# hacker-boards-refactor.net
KiCad netlist of a schematic drawn in EAGLE
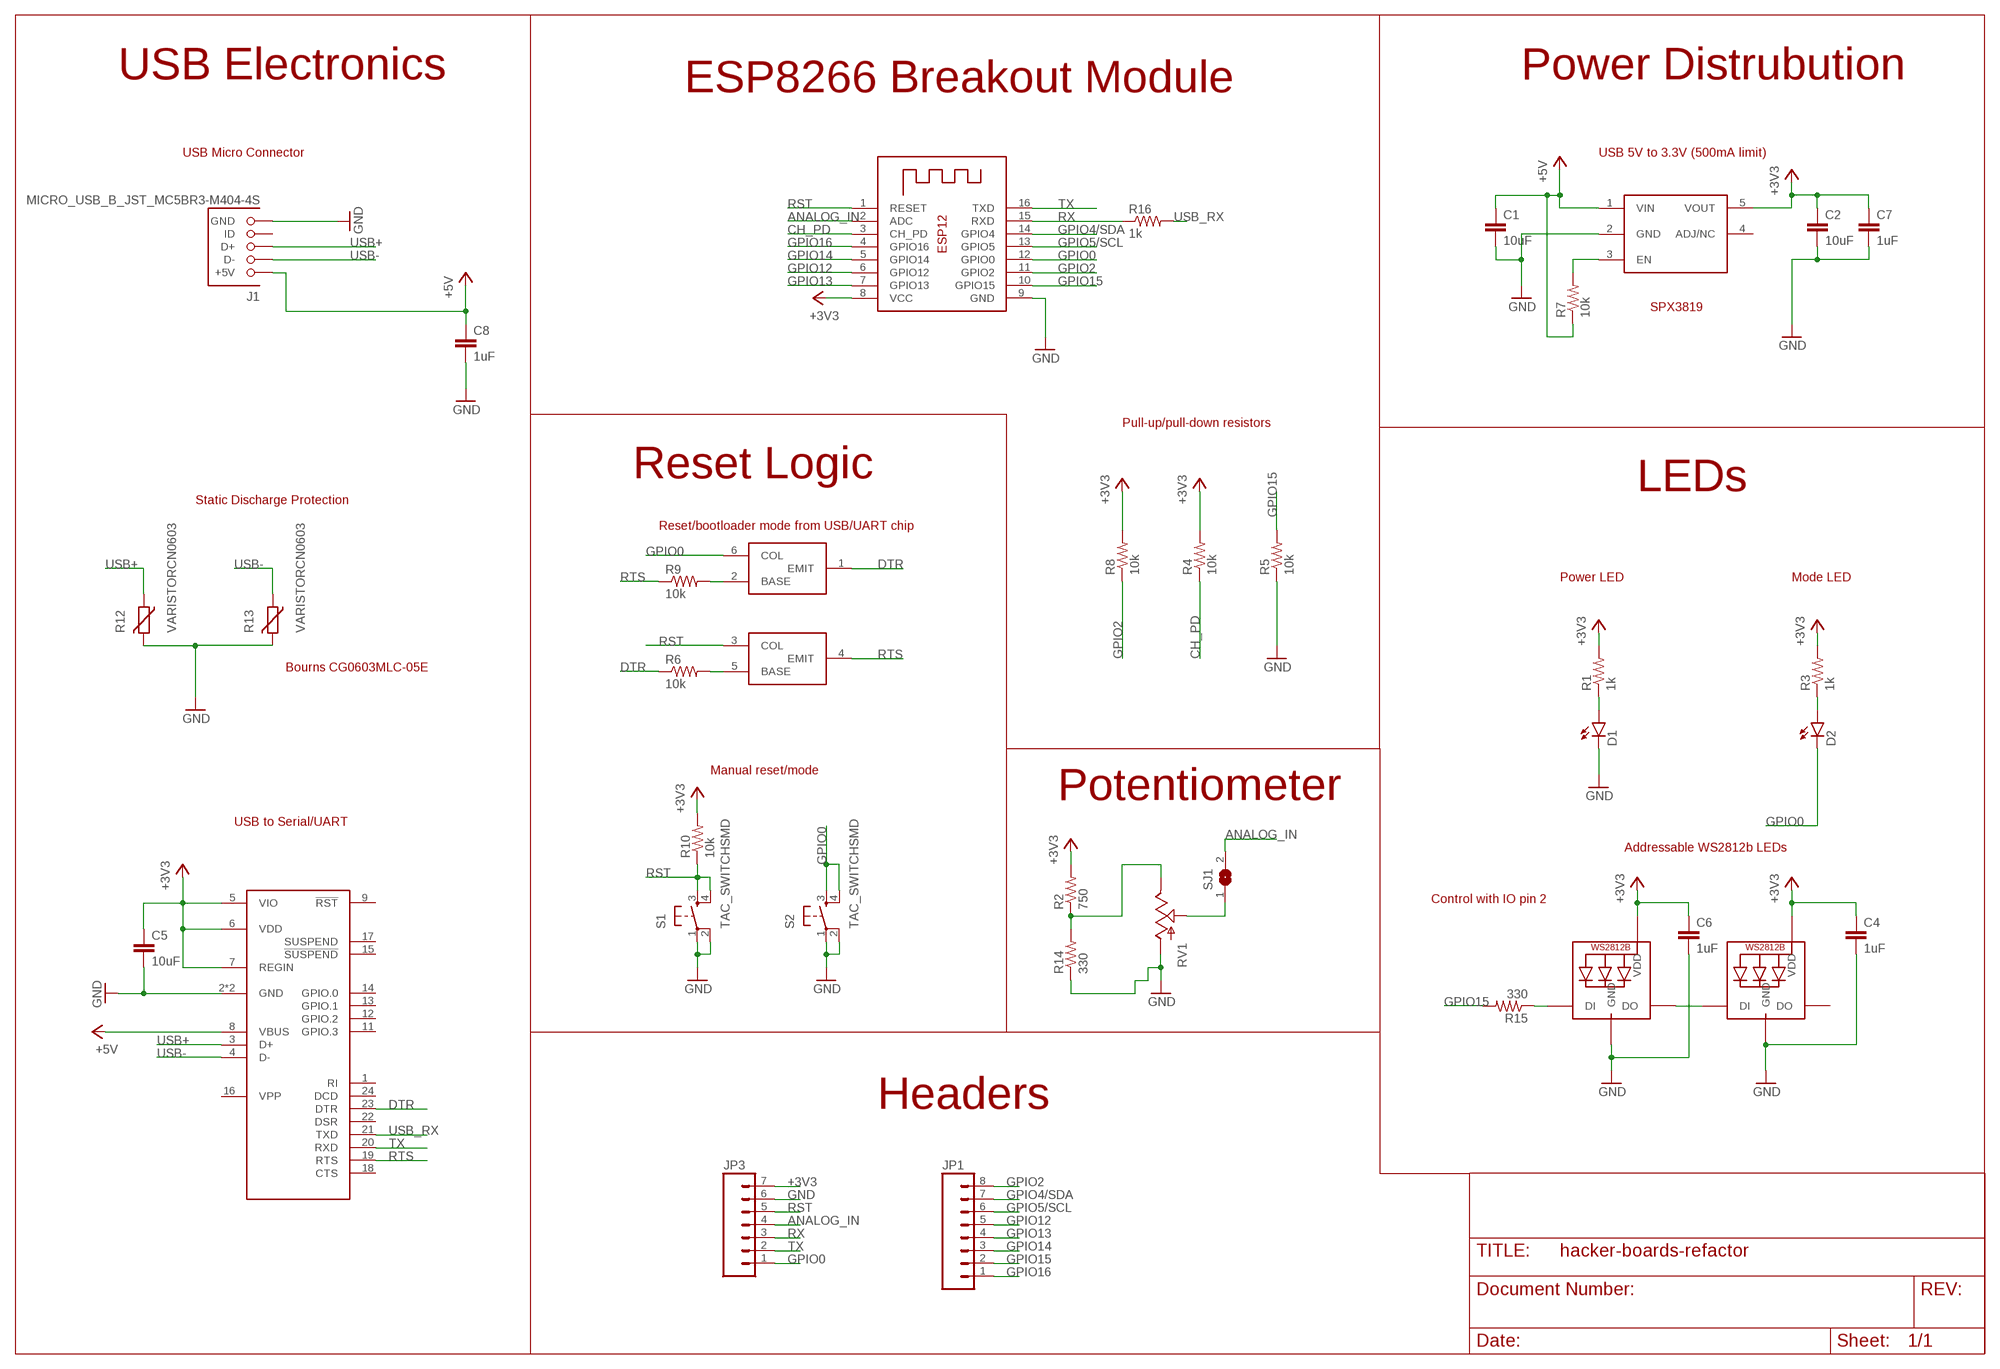
[diagram p0: schematic, sheet 1]

(export (version "E")
  (design (tool "Eeschema 10.0.6"))
  (components
    (comp (ref "C1")
      (value "10uF")
      (footprint "eagle-import:C0805")
      (libsource (lib "eagle-import") (part "C0805"))
    )
    (comp (ref "C2")
      (value "10uF")
      (footprint "eagle-import:C0805")
      (libsource (lib "eagle-import") (part "C0805"))
    )
    (comp (ref "C4")
      (value "1uF")
      (footprint "eagle-import:C0402")
      (libsource (lib "eagle-import") (part "C-EUC0402"))
    )
    (comp (ref "C5")
      (value "10uF")
      (footprint "eagle-import:C0805")
      (libsource (lib "eagle-import") (part "C0805"))
    )
    (comp (ref "C6")
      (value "1uF")
      (footprint "eagle-import:C0402")
      (libsource (lib "eagle-import") (part "C-EUC0402"))
    )
    (comp (ref "C7")
      (value "1uF")
      (footprint "eagle-import:C0402")
      (libsource (lib "eagle-import") (part "C-EUC0402"))
    )
    (comp (ref "C8")
      (value "1uF")
      (footprint "eagle-import:C0402")
      (libsource (lib "eagle-import") (part "C-EUC0402"))
    )
    (comp (ref "D1")
      (value "LED0603")
      (footprint "eagle-import:LED-0603")
      (libsource (lib "eagle-import") (part "LED0603"))
    )
    (comp (ref "D2")
      (value "LED0603")
      (footprint "eagle-import:LED-0603")
      (libsource (lib "eagle-import") (part "LED0603"))
    )
    (comp (ref "J1")
      (value "MICRO_USB_B_JST_MC5BR3-M404-4S")
      (footprint "eagle-import:USB_MICRO_B-JST-MC5BR3-M404-4S-TB")
      (libsource (lib "eagle-import") (part "MICRO_USB_B_JST_MC5BR3-M404-4S"))
    )
    (comp (ref "JP1")
      (value "M08")
      (footprint "eagle-import:1X08_ROUND")
      (libsource (lib "eagle-import") (part "M08"))
    )
    (comp (ref "JP3")
      (value "M07")
      (footprint "eagle-import:1X07")
      (libsource (lib "eagle-import") (part "M07"))
    )
    (comp (ref "LED1")
      (value "WS2812B5050")
      (footprint "eagle-import:WS2812B")
      (libsource (lib "eagle-import") (part "WS2812B5050"))
    )
    (comp (ref "LED2")
      (value "WS2812B5050")
      (footprint "eagle-import:WS2812B")
      (libsource (lib "eagle-import") (part "WS2812B5050"))
    )
    (comp (ref "R1")
      (value "1k")
      (footprint "eagle-import:R0402")
      (libsource (lib "eagle-import") (part "R-US_R0402"))
    )
    (comp (ref "R2")
      (value "750")
      (footprint "eagle-import:R0402")
      (libsource (lib "eagle-import") (part "R-US_R0402"))
    )
    (comp (ref "R3")
      (value "1k")
      (footprint "eagle-import:R0402")
      (libsource (lib "eagle-import") (part "R-US_R0402"))
    )
    (comp (ref "R4")
      (value "10k")
      (footprint "eagle-import:R0402")
      (libsource (lib "eagle-import") (part "R-US_R0402"))
    )
    (comp (ref "R5")
      (value "10k")
      (footprint "eagle-import:R0402")
      (libsource (lib "eagle-import") (part "R-US_R0402"))
    )
    (comp (ref "R6")
      (value "10k")
      (footprint "eagle-import:R0402")
      (libsource (lib "eagle-import") (part "R-US_R0402"))
    )
    (comp (ref "R7")
      (value "10k")
      (footprint "eagle-import:R0402")
      (libsource (lib "eagle-import") (part "R-US_R0402"))
    )
    (comp (ref "R8")
      (value "10k")
      (footprint "eagle-import:R0402")
      (libsource (lib "eagle-import") (part "R-US_R0402"))
    )
    (comp (ref "R9")
      (value "10k")
      (footprint "eagle-import:R0402")
      (libsource (lib "eagle-import") (part "R-US_R0402"))
    )
    (comp (ref "R10")
      (value "10k")
      (footprint "eagle-import:R0402")
      (libsource (lib "eagle-import") (part "R-US_R0402"))
    )
    (comp (ref "R12")
      (value "VARISTORCN0603")
      (footprint "eagle-import:CT_CN0603")
      (libsource (lib "eagle-import") (part "VARISTORCN0603"))
    )
    (comp (ref "R13")
      (value "VARISTORCN0603")
      (footprint "eagle-import:CT_CN0603")
      (libsource (lib "eagle-import") (part "VARISTORCN0603"))
    )
    (comp (ref "R14")
      (value "330")
      (footprint "eagle-import:R0402")
      (libsource (lib "eagle-import") (part "R-US_R0402"))
    )
    (comp (ref "R15")
      (value "330")
      (footprint "eagle-import:R0402")
      (libsource (lib "eagle-import") (part "R-US_R0402"))
    )
    (comp (ref "R16")
      (value "1k")
      (footprint "eagle-import:R0402")
      (libsource (lib "eagle-import") (part "R-US_R0402"))
    )
    (comp (ref "RV1")
      (value "POTALPS-KIT")
      (footprint "eagle-import:ALPS_POT_KIT")
      (libsource (lib "eagle-import") (part "POTALPS-KIT"))
    )
    (comp (ref "S1")
      (value "TAC_SWITCHSMD")
      (footprint "eagle-import:TACTILE-SWITCH-SMD")
      (libsource (lib "eagle-import") (part "TAC_SWITCHSMD"))
    )
    (comp (ref "S2")
      (value "TAC_SWITCHSMD")
      (footprint "eagle-import:TACTILE-SWITCH-SMD")
      (libsource (lib "eagle-import") (part "TAC_SWITCHSMD"))
    )
    (comp (ref "SJ1") (value "SJ") (footprint "eagle-import:SJ") (libsource (lib "eagle-import") (part "SJ")))
    (comp (ref "U$2")
      (value "AP2112")
      (footprint "eagle-import:SOT23-5L")
      (libsource (lib "eagle-import") (part "AP2112"))
    )
    (comp (ref "U$3")
      (value "CP2104")
      (footprint "eagle-import:QFN24_4X4")
      (libsource (lib "eagle-import") (part "CP2104"))
    )
    (comp (ref "U$4")
      (value "MBT3904DW1T1G")
      (footprint "eagle-import:SOT363")
      (libsource (lib "eagle-import") (part "MBT3904DW1T1G"))
    )
    (comp (ref "X1")
      (value "ESP-12")
      (footprint "eagle-import:ESP-12")
      (libsource (lib "eagle-import") (part "ESP-12"))
    )
  )
  (nets
    (net (code "1") (name "+3V3") (class "Default")
      (node (ref "C2") (pin "1") (pinfunction "1_1") (pintype "passive"))
      (node (ref "C4") (pin "1") (pinfunction "1_1") (pintype "passive"))
      (node (ref "C5") (pin "1") (pinfunction "1_1") (pintype "passive"))
      (node (ref "C6") (pin "1") (pinfunction "1_1") (pintype "passive"))
      (node (ref "C7") (pin "1") (pinfunction "1_1") (pintype "passive"))
      (node (ref "JP3") (pin "7") (pinfunction "7_7") (pintype "passive"))
      (node (ref "LED1") (pin "1-VDD") (pinfunction "VDD_1-VDD") (pintype "power_in"))
      (node (ref "LED2") (pin "1-VDD") (pinfunction "VDD_1-VDD") (pintype "power_in"))
      (node (ref "R1") (pin "2") (pinfunction "2_2") (pintype "passive"))
      (node (ref "R10") (pin "2") (pinfunction "2_2") (pintype "passive"))
      (node (ref "R2") (pin "2") (pinfunction "2_2") (pintype "passive"))
      (node (ref "R3") (pin "2") (pinfunction "2_2") (pintype "passive"))
      (node (ref "R4") (pin "2") (pinfunction "2_2") (pintype "passive"))
      (node (ref "R8") (pin "2") (pinfunction "2_2") (pintype "passive"))
      (node (ref "U$2") (pin "5") (pinfunction "VOUT_5") (pintype "bidirectional"))
      (node (ref "U$3") (pin "5") (pinfunction "VIO_5") (pintype "bidirectional"))
      (node (ref "U$3") (pin "6") (pinfunction "VDD_6") (pintype "bidirectional"))
      (node (ref "U$3") (pin "7") (pinfunction "REGIN_7") (pintype "bidirectional"))
      (node (ref "X1") (pin "8") (pinfunction "VCC_8") (pintype "power_in"))
    )
    (net (code "2") (name "+5V") (class "Default")
      (node (ref "C1") (pin "1") (pinfunction "1_1") (pintype "passive"))
      (node (ref "C8") (pin "1") (pinfunction "1_1") (pintype "passive"))
      (node (ref "J1") (pin "1") (pinfunction "+5V_1") (pintype "bidirectional"))
      (node (ref "R7") (pin "1") (pinfunction "1_1") (pintype "passive"))
      (node (ref "U$2") (pin "1") (pinfunction "VIN_1") (pintype "bidirectional"))
      (node (ref "U$3") (pin "8") (pinfunction "VBUS_8") (pintype "bidirectional"))
    )
    (net (code "3") (name "/ANALOG_IN") (class "Default")
      (node (ref "JP3") (pin "4") (pinfunction "4_4") (pintype "passive"))
      (node (ref "SJ1") (pin "2") (pinfunction "2_2") (pintype "passive"))
      (node (ref "X1") (pin "2") (pinfunction "ADC_2") (pintype "passive"))
    )
    (net (code "4") (name "/CH_PD") (class "Default")
      (node (ref "R4") (pin "1") (pinfunction "1_1") (pintype "passive"))
      (node (ref "X1") (pin "3") (pinfunction "CH_PD_3") (pintype "input"))
    )
    (net (code "5") (name "/DTR") (class "Default")
      (node (ref "R6") (pin "1") (pinfunction "1_1") (pintype "passive"))
      (node (ref "U$3") (pin "23") (pinfunction "DTR_23") (pintype "bidirectional"))
      (node (ref "U$4") (pin "1") (pinfunction "EMIT_1") (pintype "bidirectional"))
    )
    (net (code "6") (name "/GPIO0") (class "Default")
      (node (ref "D2") (pin "C") (pinfunction "C_C") (pintype "passive"))
      (node (ref "JP3") (pin "1") (pinfunction "1_1") (pintype "passive"))
      (node (ref "S2") (pin "3") (pinfunction "3_3") (pintype "passive"))
      (node (ref "S2") (pin "4") (pinfunction "4_4") (pintype "passive"))
      (node (ref "U$4") (pin "6") (pinfunction "COL_6") (pintype "bidirectional"))
      (node (ref "X1") (pin "12") (pinfunction "GPIO0_12") (pintype "bidirectional"))
    )
    (net (code "7") (name "/GPIO2") (class "Default")
      (node (ref "JP1") (pin "8") (pinfunction "8_8") (pintype "passive"))
      (node (ref "R8") (pin "1") (pinfunction "1_1") (pintype "passive"))
      (node (ref "X1") (pin "11") (pinfunction "GPIO2_11") (pintype "bidirectional"))
    )
    (net (code "8") (name "/GPIO4{slash}SDA") (class "Default")
      (node (ref "JP1") (pin "7") (pinfunction "7_7") (pintype "passive"))
      (node (ref "X1") (pin "14") (pinfunction "GPIO4_14") (pintype "bidirectional"))
    )
    (net (code "9") (name "/GPIO5{slash}SCL") (class "Default")
      (node (ref "JP1") (pin "6") (pinfunction "6_6") (pintype "passive"))
      (node (ref "X1") (pin "13") (pinfunction "GPIO5_13") (pintype "bidirectional"))
    )
    (net (code "10") (name "/GPIO12") (class "Default")
      (node (ref "JP1") (pin "5") (pinfunction "5_5") (pintype "passive"))
      (node (ref "X1") (pin "6") (pinfunction "GPIO12_6") (pintype "bidirectional"))
    )
    (net (code "11") (name "/GPIO13") (class "Default")
      (node (ref "JP1") (pin "4") (pinfunction "4_4") (pintype "passive"))
      (node (ref "X1") (pin "7") (pinfunction "GPIO13_7") (pintype "bidirectional"))
    )
    (net (code "12") (name "/GPIO14") (class "Default")
      (node (ref "JP1") (pin "3") (pinfunction "3_3") (pintype "passive"))
      (node (ref "X1") (pin "5") (pinfunction "GPIO14_5") (pintype "bidirectional"))
    )
    (net (code "13") (name "/GPIO15") (class "Default")
      (node (ref "JP1") (pin "2") (pinfunction "2_2") (pintype "passive"))
      (node (ref "R15") (pin "2") (pinfunction "2_2") (pintype "passive"))
      (node (ref "R5") (pin "2") (pinfunction "2_2") (pintype "passive"))
      (node (ref "X1") (pin "10") (pinfunction "GPIO15_10") (pintype "bidirectional"))
    )
    (net (code "14") (name "/GPIO16") (class "Default")
      (node (ref "JP1") (pin "1") (pinfunction "1_1") (pintype "passive"))
      (node (ref "X1") (pin "4") (pinfunction "GPIO16_4") (pintype "bidirectional"))
    )
    (net (code "15") (name "/RST") (class "Default")
      (node (ref "JP3") (pin "5") (pinfunction "5_5") (pintype "passive"))
      (node (ref "R10") (pin "1") (pinfunction "1_1") (pintype "passive"))
      (node (ref "S1") (pin "3") (pinfunction "3_3") (pintype "passive"))
      (node (ref "S1") (pin "4") (pinfunction "4_4") (pintype "passive"))
      (node (ref "U$4") (pin "3") (pinfunction "COL_3") (pintype "bidirectional"))
      (node (ref "X1") (pin "1") (pinfunction "RESET_1") (pintype "input"))
    )
    (net (code "16") (name "/RTS") (class "Default")
      (node (ref "R9") (pin "1") (pinfunction "1_1") (pintype "passive"))
      (node (ref "U$3") (pin "19") (pinfunction "RTS_19") (pintype "bidirectional"))
      (node (ref "U$4") (pin "4") (pinfunction "EMIT_4") (pintype "bidirectional"))
    )
    (net (code "17") (name "/RX") (class "Default")
      (node (ref "JP3") (pin "3") (pinfunction "3_3") (pintype "passive"))
      (node (ref "R16") (pin "1") (pinfunction "1_1") (pintype "passive"))
      (node (ref "X1") (pin "15") (pinfunction "RXD_15") (pintype "input"))
    )
    (net (code "18") (name "/TX") (class "Default")
      (node (ref "JP3") (pin "2") (pinfunction "2_2") (pintype "passive"))
      (node (ref "U$3") (pin "20") (pinfunction "RXD_20") (pintype "bidirectional"))
      (node (ref "X1") (pin "16") (pinfunction "TXD_16") (pintype "output"))
    )
    (net (code "19") (name "/USB+") (class "Default")
      (node (ref "J1") (pin "3") (pinfunction "D+_3") (pintype "bidirectional"))
      (node (ref "R12") (pin "1") (pinfunction "1_1") (pintype "passive"))
      (node (ref "U$3") (pin "3") (pinfunction "D+_3") (pintype "bidirectional"))
    )
    (net (code "20") (name "/USB-") (class "Default")
      (node (ref "J1") (pin "2") (pinfunction "D-_2") (pintype "bidirectional"))
      (node (ref "R13") (pin "1") (pinfunction "1_1") (pintype "passive"))
      (node (ref "U$3") (pin "4") (pinfunction "D-_4") (pintype "bidirectional"))
    )
    (net (code "21") (name "/USB_RX") (class "Default")
      (node (ref "R16") (pin "2") (pinfunction "2_2") (pintype "passive"))
      (node (ref "U$3") (pin "21") (pinfunction "TXD_21") (pintype "bidirectional"))
    )
    (net (code "22") (name "GND") (class "Default")
      (node (ref "C1") (pin "2") (pinfunction "2_2") (pintype "passive"))
      (node (ref "C2") (pin "2") (pinfunction "2_2") (pintype "passive"))
      (node (ref "C4") (pin "2") (pinfunction "2_2") (pintype "passive"))
      (node (ref "C5") (pin "2") (pinfunction "2_2") (pintype "passive"))
      (node (ref "C6") (pin "2") (pinfunction "2_2") (pintype "passive"))
      (node (ref "C7") (pin "2") (pinfunction "2_2") (pintype "passive"))
      (node (ref "C8") (pin "2") (pinfunction "2_2") (pintype "passive"))
      (node (ref "D1") (pin "C") (pinfunction "C_C") (pintype "passive"))
      (node (ref "J1") (pin "5") (pinfunction "GND_5") (pintype "bidirectional"))
      (node (ref "JP3") (pin "6") (pinfunction "6_6") (pintype "passive"))
      (node (ref "LED1") (pin "3-GND") (pinfunction "GND_3-GND") (pintype "power_in"))
      (node (ref "LED2") (pin "3-GND") (pinfunction "GND_3-GND") (pintype "power_in"))
      (node (ref "R12") (pin "2") (pinfunction "2_2") (pintype "passive"))
      (node (ref "R13") (pin "2") (pinfunction "2_2") (pintype "passive"))
      (node (ref "R14") (pin "1") (pinfunction "1_1") (pintype "passive"))
      (node (ref "R5") (pin "1") (pinfunction "1_1") (pintype "passive"))
      (node (ref "RV1") (pin "P$3") (pinfunction "A_P$3") (pintype "passive"))
      (node (ref "S1") (pin "1") (pinfunction "1_1") (pintype "passive"))
      (node (ref "S1") (pin "2") (pinfunction "2_2") (pintype "passive"))
      (node (ref "S2") (pin "1") (pinfunction "1_1") (pintype "passive"))
      (node (ref "S2") (pin "2") (pinfunction "2_2") (pintype "passive"))
      (node (ref "U$2") (pin "2") (pinfunction "GND_2") (pintype "bidirectional"))
      (node (ref "U$3") (pin "2") (pinfunction "GND_2") (pintype "bidirectional"))
      (node (ref "U$3") (pin "25") (pinfunction "GND_25") (pintype "bidirectional"))
      (node (ref "X1") (pin "9") (pinfunction "GND_9") (pintype "power_in"))
    )
    (net (code "23") (name "Net-(D1-PadA)") (class "Default")
      (node (ref "D1") (pin "A") (pinfunction "A_A") (pintype "passive"))
      (node (ref "R1") (pin "1") (pinfunction "1_1") (pintype "passive"))
    )
    (net (code "24") (name "Net-(D2-PadA)") (class "Default")
      (node (ref "D2") (pin "A") (pinfunction "A_A") (pintype "passive"))
      (node (ref "R3") (pin "1") (pinfunction "1_1") (pintype "passive"))
    )
    (net (code "25") (name "Net-(LED1-DI)") (class "Default")
      (node (ref "LED1") (pin "4-DIN") (pinfunction "DI_4-DIN") (pintype "input"))
      (node (ref "R15") (pin "1") (pinfunction "1_1") (pintype "passive"))
    )
    (net (code "26") (name "Net-(LED1-DO)") (class "Default")
      (node (ref "LED1") (pin "2-DOUT") (pinfunction "DO_2-DOUT") (pintype "output"))
      (node (ref "LED2") (pin "4-DIN") (pinfunction "DI_4-DIN") (pintype "input"))
    )
    (net (code "27") (name "Net-(RV1-E)") (class "Default")
      (node (ref "R14") (pin "2") (pinfunction "2_2") (pintype "passive"))
      (node (ref "R2") (pin "1") (pinfunction "1_1") (pintype "passive"))
      (node (ref "RV1") (pin "P$1") (pinfunction "E_P$1") (pintype "passive"))
    )
    (net (code "28") (name "Net-(RV1-S)") (class "Default")
      (node (ref "RV1") (pin "P$2") (pinfunction "S_P$2") (pintype "passive"))
      (node (ref "SJ1") (pin "1") (pinfunction "1_1") (pintype "passive"))
    )
    (net (code "29") (name "Net-(U$2-EN)") (class "Default")
      (node (ref "R7") (pin "2") (pinfunction "2_2") (pintype "passive"))
      (node (ref "U$2") (pin "3") (pinfunction "EN_3") (pintype "bidirectional"))
    )
    (net (code "30") (name "Net-(U$4A-BASE)") (class "Default")
      (node (ref "R9") (pin "2") (pinfunction "2_2") (pintype "passive"))
      (node (ref "U$4") (pin "2") (pinfunction "BASE_2") (pintype "bidirectional"))
    )
    (net (code "31") (name "Net-(U$4B-BASE)") (class "Default")
      (node (ref "R6") (pin "2") (pinfunction "2_2") (pintype "passive"))
      (node (ref "U$4") (pin "5") (pinfunction "BASE_5") (pintype "bidirectional"))
    )
    (net (code "32") (name "unconnected-(J1-ID-Pad4)") (class "Default")
      (node (ref "J1") (pin "4") (pinfunction "ID_4") (pintype "bidirectional"))
    )
    (net (code "33") (name "unconnected-(LED2-DO-Pad2-DOUT)") (class "Default")
      (node (ref "LED2") (pin "2-DOUT") (pinfunction "DO_2-DOUT") (pintype "output"))
    )
    (net (code "34") (name "unconnected-(U$2-ADJ{slash}NC-Pad4)") (class "Default")
      (node (ref "U$2") (pin "4") (pinfunction "ADJ/NC_4") (pintype "bidirectional"))
    )
    (net (code "35") (name "unconnected-(U$3-CTS-Pad18)") (class "Default")
      (node (ref "U$3") (pin "18") (pinfunction "CTS_18") (pintype "bidirectional"))
    )
    (net (code "36") (name "unconnected-(U$3-DCD-Pad24)") (class "Default")
      (node (ref "U$3") (pin "24") (pinfunction "DCD_24") (pintype "bidirectional"))
    )
    (net (code "37") (name "unconnected-(U$3-DSR-Pad22)") (class "Default")
      (node (ref "U$3") (pin "22") (pinfunction "DSR_22") (pintype "bidirectional"))
    )
    (net (code "38") (name "unconnected-(U$3-GPIO.0-Pad14)") (class "Default")
      (node (ref "U$3") (pin "14") (pinfunction "GPIO.0_14") (pintype "bidirectional"))
    )
    (net (code "39") (name "unconnected-(U$3-GPIO.1-Pad13)") (class "Default")
      (node (ref "U$3") (pin "13") (pinfunction "GPIO.1_13") (pintype "bidirectional"))
    )
    (net (code "40") (name "unconnected-(U$3-GPIO.2-Pad12)") (class "Default")
      (node (ref "U$3") (pin "12") (pinfunction "GPIO.2_12") (pintype "bidirectional"))
    )
    (net (code "41") (name "unconnected-(U$3-GPIO.3-Pad11)") (class "Default")
      (node (ref "U$3") (pin "11") (pinfunction "GPIO.3_11") (pintype "bidirectional"))
    )
    (net (code "42") (name "unconnected-(U$3-RI-Pad1)") (class "Default")
      (node (ref "U$3") (pin "1") (pinfunction "RI_1") (pintype "bidirectional"))
    )
    (net (code "43") (name "unconnected-(U$3-SUSPEND-Pad17)") (class "Default")
      (node (ref "U$3") (pin "17") (pinfunction "SUSPEND_17") (pintype "bidirectional"))
    )
    (net (code "44") (name "unconnected-(U$3-VPP-Pad16)") (class "Default")
      (node (ref "U$3") (pin "16") (pinfunction "VPP_16") (pintype "input"))
    )
    (net (code "45") (name "unconnected-(U$3-~{RST}-Pad9)") (class "Default")
      (node (ref "U$3") (pin "9") (pinfunction "~{RST}_9") (pintype "bidirectional"))
    )
    (net (code "46") (name "unconnected-(U$3-~{SUSPEND}-Pad15)") (class "Default")
      (node (ref "U$3") (pin "15") (pinfunction "~{SUSPEND}_15") (pintype "bidirectional"))
    )
  )
)
